# 05-nRF52840.net
KiCad netlist of a schematic drawn in Altium Designer
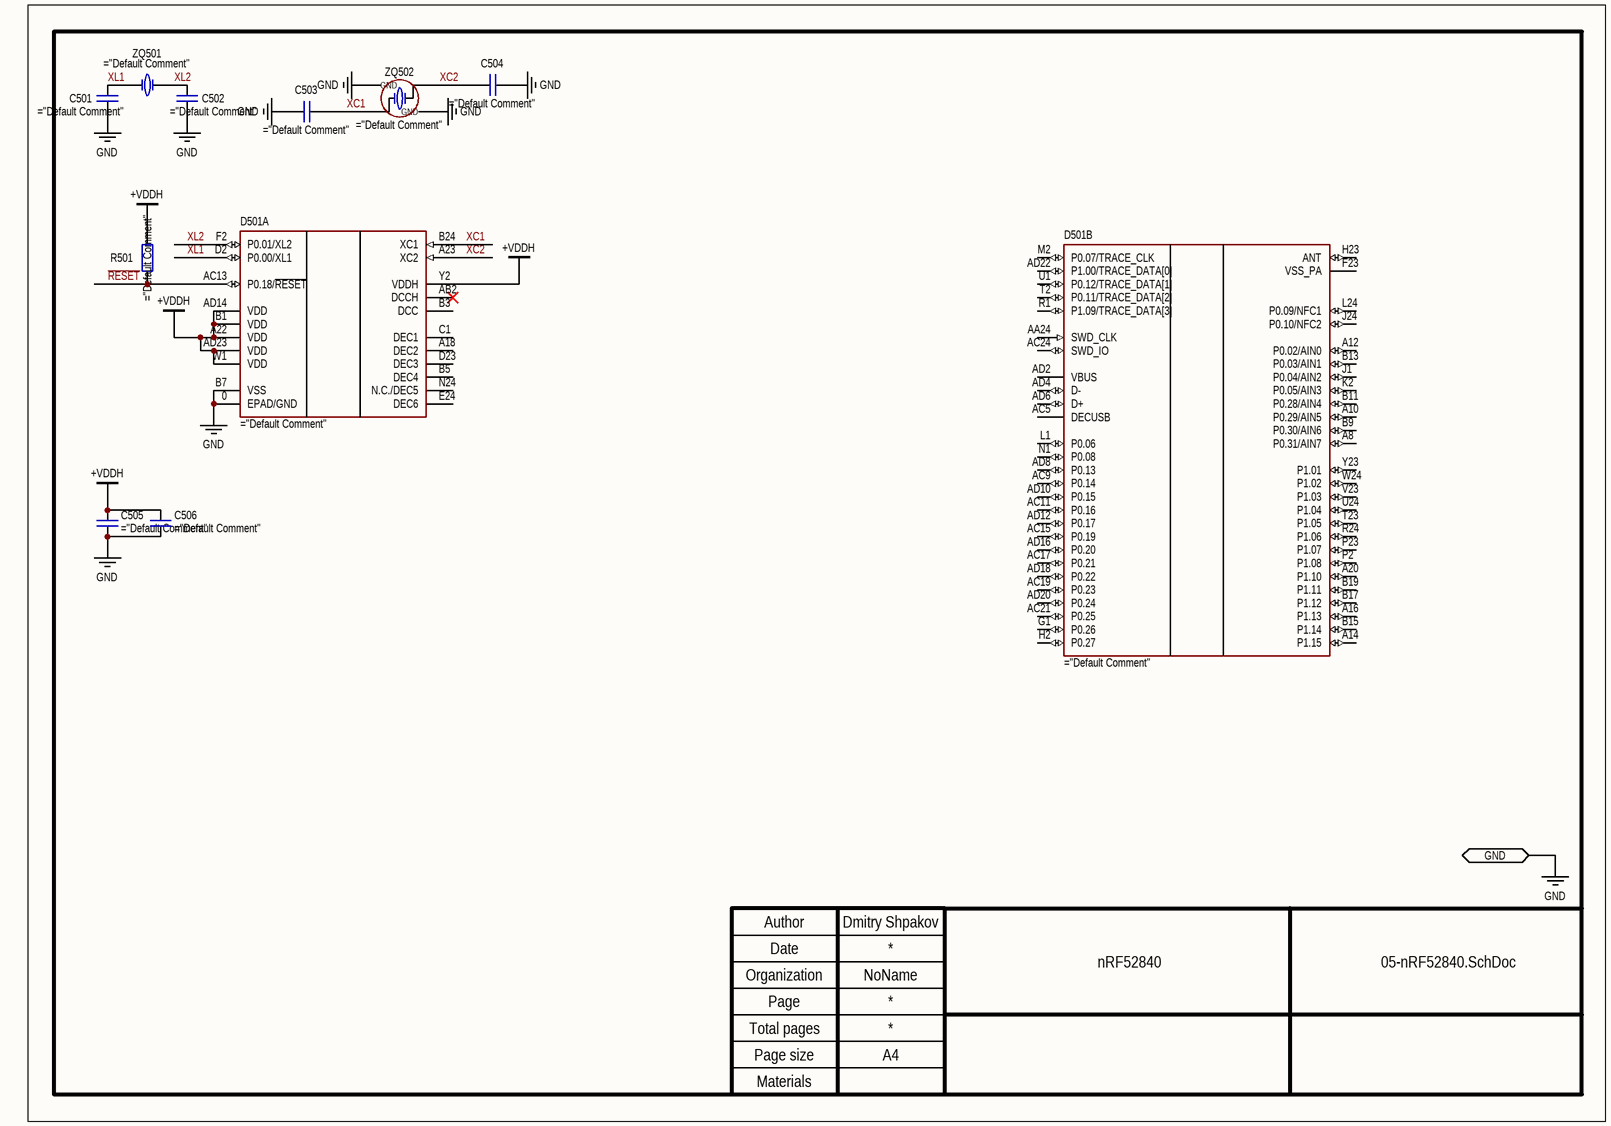
[diagram p0: 05-nRF52840.SchDoc]

(export (version "E")
  (design (tool "Eeschema 10.0.6"))
  (components
    (comp (ref "C501")
      (value "~")
      (footprint "CAP0402MD")
      (description "CAP CER 12PF 50V C0G/NPO 0402")
      (fields (field (name "MANUFACTURER") "YAGEO") (field (name "TOLERANCE") "5 %"))
      (libsource (lib "Capacitors") (part "CC0402JRNPO9BN120"))
    )
    (comp (ref "C502")
      (value "~")
      (footprint "CAP0402MD")
      (description "CAP CER 12PF 50V C0G/NPO 0402")
      (fields (field (name "MANUFACTURER") "YAGEO") (field (name "TOLERANCE") "5 %"))
      (libsource (lib "Capacitors") (part "CC0402JRNPO9BN120"))
    )
    (comp (ref "C503")
      (value "~")
      (footprint "CAP0402MD")
      (description "CAP CER 12PF 50V C0G/NPO 0402")
      (fields (field (name "MANUFACTURER") "YAGEO") (field (name "TOLERANCE") "5 %"))
      (libsource (lib "Capacitors") (part "CC0402JRNPO9BN120"))
    )
    (comp (ref "C504")
      (value "~")
      (footprint "CAP0402MD")
      (description "CAP CER 12PF 50V C0G/NPO 0402")
      (fields (field (name "MANUFACTURER") "YAGEO") (field (name "TOLERANCE") "5 %"))
      (libsource (lib "Capacitors") (part "CC0402JRNPO9BN120"))
    )
    (comp (ref "C505")
      (value "~")
      (footprint "CAP0603HD")
      (description "CAP CER 0.1UF 16V X7R 0603")
      (fields (field (name "MANUFACTURER") "YAGEO") (field (name "TOLERANCE") "10 %"))
      (libsource (lib "Capacitors") (part "CC0603KRX7R7BB104"))
    )
    (comp (ref "C506")
      (value "~")
      (footprint "CAP0603HD")
      (description "CAP CER 0.1UF 16V X7R 0603")
      (fields (field (name "MANUFACTURER") "YAGEO") (field (name "TOLERANCE") "10 %"))
      (libsource (lib "Capacitors") (part "CC0603KRX7R7BB104"))
    )
    (comp (ref "D501")
      (value "~")
      (footprint "nRF52840-QIAA")
      (description "IC RF TXRX+MCU 802.15.4 73VFQFN")
      (fields (field (name "MANUFACTURER") "Nordic Semiconductor ASA") (field (name "TOLERANCE") "* %"))
      (libsource (lib "ICs") (part "NRF52840-QIAA-R7"))
    )
    (comp (ref "R501")
      (value "~")
      (footprint "0402")
      (description "RES 10K OHM 5% 1/16W 0402")
      (fields (field (name "MANUFACTURER") "YAGEO") (field (name "TOLERANCE") "5 %"))
      (libsource (lib "Resistors") (part "RC0402JR-0710KL"))
    )
    (comp (ref "ZQ501")
      (value "~")
      (footprint "ECS-.327-9-16-TR")
      (description "CRYSTAL 32.7680KHZ 9PF SMD")
      (fields (field (name "MANUFACTURER") "ECS Inc.") (field (name "TOLERANCE") "20 ppm"))
      (libsource (lib "Oscillators") (part "ECS-.327-9-16-TR"))
    )
    (comp (ref "ZQ502")
      (value "~")
      (footprint "ECS-320-8-37B-CKY-TR")
      (description "CRYSTAL 32.0000MHZ 8PF SMD")
      (fields (field (name "MANUFACTURER") "ECS Inc.") (field (name "TOLERANCE") "10 ppm"))
      (libsource (lib "Oscillators") (part "ECS-320-8-37B-CKY-TR"))
    )
  )
  (nets
    (net (code "1") (name "+VDDH") (class "Default")
      (node (ref "C505") (pin "2") (pintype "passive"))
      (node (ref "C506") (pin "2") (pintype "passive"))
      (node (ref "D501") (pin "A22") (pinfunction "VDD_A22") (pintype "power_in"))
      (node (ref "D501") (pin "AD14") (pinfunction "VDD_AD14") (pintype "power_in"))
      (node (ref "D501") (pin "AD23") (pinfunction "VDD_AD23") (pintype "power_in"))
      (node (ref "D501") (pin "B1") (pinfunction "VDD_B1") (pintype "power_in"))
      (node (ref "D501") (pin "W1") (pinfunction "VDD_W1") (pintype "power_in"))
      (node (ref "D501") (pin "Y2") (pinfunction "VDDH_Y2") (pintype "power_in"))
      (node (ref "R501") (pin "2") (pinfunction "2_2") (pintype "passive"))
    )
    (net (code "2") (name "/RESET") (class "Default")
      (node (ref "D501") (pin "AC13") (pinfunction "P0.18/~{RESET}_AC13") (pintype "bidirectional"))
      (node (ref "R501") (pin "1") (pinfunction "1_1") (pintype "passive"))
    )
    (net (code "3") (name "/XC1") (class "Default")
      (node (ref "C503") (pin "2") (pintype "passive"))
      (node (ref "D501") (pin "B24") (pinfunction "XC1_B24") (pintype "input"))
      (node (ref "ZQ502") (pin "1") (pinfunction "1_1") (pintype "passive"))
    )
    (net (code "4") (name "/XC2") (class "Default")
      (node (ref "C504") (pin "2") (pintype "passive"))
      (node (ref "D501") (pin "A23") (pinfunction "XC2_A23") (pintype "input"))
      (node (ref "ZQ502") (pin "3") (pinfunction "3_3") (pintype "passive"))
    )
    (net (code "5") (name "/XL1") (class "Default")
      (node (ref "C501") (pin "2") (pintype "passive"))
      (node (ref "D501") (pin "D2") (pinfunction "P0.00/XL1_D2") (pintype "bidirectional"))
      (node (ref "ZQ501") (pin "2") (pinfunction "2_2") (pintype "passive"))
    )
    (net (code "6") (name "/XL2") (class "Default")
      (node (ref "C502") (pin "2") (pintype "passive"))
      (node (ref "D501") (pin "F2") (pinfunction "P0.01/XL2_F2") (pintype "bidirectional"))
      (node (ref "ZQ501") (pin "1") (pinfunction "1_1") (pintype "passive"))
    )
    (net (code "7") (name "GND") (class "Default")
      (node (ref "C501") (pin "1") (pintype "passive"))
      (node (ref "C502") (pin "1") (pintype "passive"))
      (node (ref "C503") (pin "1") (pintype "passive"))
      (node (ref "C504") (pin "1") (pintype "passive"))
      (node (ref "C505") (pin "1") (pintype "passive"))
      (node (ref "C506") (pin "1") (pintype "passive"))
      (node (ref "D501") (pin "0") (pinfunction "EPAD/GND_0") (pintype "passive"))
      (node (ref "D501") (pin "B7") (pinfunction "VSS_B7") (pintype "passive"))
      (node (ref "ZQ502") (pin "2") (pinfunction "2_2") (pintype "passive"))
      (node (ref "ZQ502") (pin "4") (pinfunction "4_4") (pintype "passive"))
    )
    (net (code "8") (name "unconnected-(D501A-DCC-PadB3)") (class "Default")
      (node (ref "D501") (pin "B3") (pinfunction "DCC_B3") (pintype "power_in"))
    )
    (net (code "9") (name "unconnected-(D501A-DCCH-PadAB2)") (class "Default")
      (node (ref "D501") (pin "AB2") (pinfunction "DCCH_AB2") (pintype "power_in+no_connect"))
    )
    (net (code "10") (name "unconnected-(D501A-DEC1-PadC1)") (class "Default")
      (node (ref "D501") (pin "C1") (pinfunction "DEC1_C1") (pintype "power_in"))
    )
    (net (code "11") (name "unconnected-(D501A-DEC2-PadA18)") (class "Default")
      (node (ref "D501") (pin "A18") (pinfunction "DEC2_A18") (pintype "power_in"))
    )
    (net (code "12") (name "unconnected-(D501A-DEC3-PadD23)") (class "Default")
      (node (ref "D501") (pin "D23") (pinfunction "DEC3_D23") (pintype "power_in"))
    )
    (net (code "13") (name "unconnected-(D501A-DEC4-PadB5)") (class "Default")
      (node (ref "D501") (pin "B5") (pinfunction "DEC4_B5") (pintype "power_in"))
    )
    (net (code "14") (name "unconnected-(D501A-DEC6-PadE24)") (class "Default")
      (node (ref "D501") (pin "E24") (pinfunction "DEC6_E24") (pintype "power_in"))
    )
    (net (code "15") (name "unconnected-(D501A-N.C.{slash}DEC5-PadN24)") (class "Default")
      (node (ref "D501") (pin "N24") (pinfunction "N.C./DEC5_N24") (pintype "power_in"))
    )
    (net (code "16") (name "unconnected-(D501B-ANT-PadH23)") (class "Default")
      (node (ref "D501") (pin "H23") (pinfunction "ANT_H23") (pintype "bidirectional"))
    )
    (net (code "17") (name "unconnected-(D501B-D+-PadAD6)") (class "Default")
      (node (ref "D501") (pin "AD6") (pinfunction "D+_AD6") (pintype "bidirectional"))
    )
    (net (code "18") (name "unconnected-(D501B-D--PadAD4)") (class "Default")
      (node (ref "D501") (pin "AD4") (pinfunction "D-_AD4") (pintype "bidirectional"))
    )
    (net (code "19") (name "unconnected-(D501B-DECUSB-PadAC5)") (class "Default")
      (node (ref "D501") (pin "AC5") (pinfunction "DECUSB_AC5") (pintype "power_in"))
    )
    (net (code "20") (name "unconnected-(D501B-P0.02{slash}AIN0-PadA12)") (class "Default")
      (node (ref "D501") (pin "A12") (pinfunction "P0.02/AIN0_A12") (pintype "bidirectional"))
    )
    (net (code "21") (name "unconnected-(D501B-P0.03{slash}AIN1-PadB13)") (class "Default")
      (node (ref "D501") (pin "B13") (pinfunction "P0.03/AIN1_B13") (pintype "bidirectional"))
    )
    (net (code "22") (name "unconnected-(D501B-P0.04{slash}AIN2-PadJ1)") (class "Default")
      (node (ref "D501") (pin "J1") (pinfunction "P0.04/AIN2_J1") (pintype "bidirectional"))
    )
    (net (code "23") (name "unconnected-(D501B-P0.05{slash}AIN3-PadK2)") (class "Default")
      (node (ref "D501") (pin "K2") (pinfunction "P0.05/AIN3_K2") (pintype "bidirectional"))
    )
    (net (code "24") (name "unconnected-(D501B-P0.06-PadL1)") (class "Default")
      (node (ref "D501") (pin "L1") (pinfunction "P0.06_L1") (pintype "bidirectional"))
    )
    (net (code "25") (name "unconnected-(D501B-P0.07{slash}TRACE_CLK-PadM2)") (class "Default")
      (node (ref "D501") (pin "M2") (pinfunction "P0.07/TRACE_CLK_M2") (pintype "bidirectional"))
    )
    (net (code "26") (name "unconnected-(D501B-P0.08-PadN1)") (class "Default")
      (node (ref "D501") (pin "N1") (pinfunction "P0.08_N1") (pintype "bidirectional"))
    )
    (net (code "27") (name "unconnected-(D501B-P0.09{slash}NFC1-PadL24)") (class "Default")
      (node (ref "D501") (pin "L24") (pinfunction "P0.09/NFC1_L24") (pintype "bidirectional"))
    )
    (net (code "28") (name "unconnected-(D501B-P0.10{slash}NFC2-PadJ24)") (class "Default")
      (node (ref "D501") (pin "J24") (pinfunction "P0.10/NFC2_J24") (pintype "bidirectional"))
    )
    (net (code "29") (name "unconnected-(D501B-P0.11{slash}TRACE_DATA[2]-PadT2)") (class "Default")
      (node (ref "D501") (pin "T2") (pinfunction "P0.11/TRACE_DATA[2]_T2") (pintype "bidirectional"))
    )
    (net (code "30") (name "unconnected-(D501B-P0.12{slash}TRACE_DATA[1]-PadU1)") (class "Default")
      (node (ref "D501") (pin "U1") (pinfunction "P0.12/TRACE_DATA[1]_U1") (pintype "bidirectional"))
    )
    (net (code "31") (name "unconnected-(D501B-P0.13-PadAD8)") (class "Default")
      (node (ref "D501") (pin "AD8") (pinfunction "P0.13_AD8") (pintype "bidirectional"))
    )
    (net (code "32") (name "unconnected-(D501B-P0.14-PadAC9)") (class "Default")
      (node (ref "D501") (pin "AC9") (pinfunction "P0.14_AC9") (pintype "bidirectional"))
    )
    (net (code "33") (name "unconnected-(D501B-P0.15-PadAD10)") (class "Default")
      (node (ref "D501") (pin "AD10") (pinfunction "P0.15_AD10") (pintype "bidirectional"))
    )
    (net (code "34") (name "unconnected-(D501B-P0.16-PadAC11)") (class "Default")
      (node (ref "D501") (pin "AC11") (pinfunction "P0.16_AC11") (pintype "bidirectional"))
    )
    (net (code "35") (name "unconnected-(D501B-P0.17-PadAD12)") (class "Default")
      (node (ref "D501") (pin "AD12") (pinfunction "P0.17_AD12") (pintype "bidirectional"))
    )
    (net (code "36") (name "unconnected-(D501B-P0.19-PadAC15)") (class "Default")
      (node (ref "D501") (pin "AC15") (pinfunction "P0.19_AC15") (pintype "bidirectional"))
    )
    (net (code "37") (name "unconnected-(D501B-P0.20-PadAD16)") (class "Default")
      (node (ref "D501") (pin "AD16") (pinfunction "P0.20_AD16") (pintype "bidirectional"))
    )
    (net (code "38") (name "unconnected-(D501B-P0.21-PadAC17)") (class "Default")
      (node (ref "D501") (pin "AC17") (pinfunction "P0.21_AC17") (pintype "bidirectional"))
    )
    (net (code "39") (name "unconnected-(D501B-P0.22-PadAD18)") (class "Default")
      (node (ref "D501") (pin "AD18") (pinfunction "P0.22_AD18") (pintype "bidirectional"))
    )
    (net (code "40") (name "unconnected-(D501B-P0.23-PadAC19)") (class "Default")
      (node (ref "D501") (pin "AC19") (pinfunction "P0.23_AC19") (pintype "bidirectional"))
    )
    (net (code "41") (name "unconnected-(D501B-P0.24-PadAD20)") (class "Default")
      (node (ref "D501") (pin "AD20") (pinfunction "P0.24_AD20") (pintype "bidirectional"))
    )
    (net (code "42") (name "unconnected-(D501B-P0.25-PadAC21)") (class "Default")
      (node (ref "D501") (pin "AC21") (pinfunction "P0.25_AC21") (pintype "bidirectional"))
    )
    (net (code "43") (name "unconnected-(D501B-P0.26-PadG1)") (class "Default")
      (node (ref "D501") (pin "G1") (pinfunction "P0.26_G1") (pintype "bidirectional"))
    )
    (net (code "44") (name "unconnected-(D501B-P0.27-PadH2)") (class "Default")
      (node (ref "D501") (pin "H2") (pinfunction "P0.27_H2") (pintype "bidirectional"))
    )
    (net (code "45") (name "unconnected-(D501B-P0.28{slash}AIN4-PadB11)") (class "Default")
      (node (ref "D501") (pin "B11") (pinfunction "P0.28/AIN4_B11") (pintype "bidirectional"))
    )
    (net (code "46") (name "unconnected-(D501B-P0.29{slash}AIN5-PadA10)") (class "Default")
      (node (ref "D501") (pin "A10") (pinfunction "P0.29/AIN5_A10") (pintype "bidirectional"))
    )
    (net (code "47") (name "unconnected-(D501B-P0.30{slash}AIN6-PadB9)") (class "Default")
      (node (ref "D501") (pin "B9") (pinfunction "P0.30/AIN6_B9") (pintype "bidirectional"))
    )
    (net (code "48") (name "unconnected-(D501B-P0.31{slash}AIN7-PadA8)") (class "Default")
      (node (ref "D501") (pin "A8") (pinfunction "P0.31/AIN7_A8") (pintype "bidirectional"))
    )
    (net (code "49") (name "unconnected-(D501B-P1.00{slash}TRACE_DATA[0]-PadAD22)") (class "Default")
      (node (ref "D501") (pin "AD22") (pinfunction "P1.00/TRACE_DATA[0]_AD22") (pintype "bidirectional"))
    )
    (net (code "50") (name "unconnected-(D501B-P1.01-PadY23)") (class "Default")
      (node (ref "D501") (pin "Y23") (pinfunction "P1.01_Y23") (pintype "bidirectional"))
    )
    (net (code "51") (name "unconnected-(D501B-P1.02-PadW24)") (class "Default")
      (node (ref "D501") (pin "W24") (pinfunction "P1.02_W24") (pintype "bidirectional"))
    )
    (net (code "52") (name "unconnected-(D501B-P1.03-PadV23)") (class "Default")
      (node (ref "D501") (pin "V23") (pinfunction "P1.03_V23") (pintype "bidirectional"))
    )
    (net (code "53") (name "unconnected-(D501B-P1.04-PadU24)") (class "Default")
      (node (ref "D501") (pin "U24") (pinfunction "P1.04_U24") (pintype "bidirectional"))
    )
    (net (code "54") (name "unconnected-(D501B-P1.05-PadT23)") (class "Default")
      (node (ref "D501") (pin "T23") (pinfunction "P1.05_T23") (pintype "bidirectional"))
    )
    (net (code "55") (name "unconnected-(D501B-P1.06-PadR24)") (class "Default")
      (node (ref "D501") (pin "R24") (pinfunction "P1.06_R24") (pintype "bidirectional"))
    )
    (net (code "56") (name "unconnected-(D501B-P1.07-PadP23)") (class "Default")
      (node (ref "D501") (pin "P23") (pinfunction "P1.07_P23") (pintype "bidirectional"))
    )
    (net (code "57") (name "unconnected-(D501B-P1.08-PadP2)") (class "Default")
      (node (ref "D501") (pin "P2") (pinfunction "P1.08_P2") (pintype "bidirectional"))
    )
    (net (code "58") (name "unconnected-(D501B-P1.09{slash}TRACE_DATA[3]-PadR1)") (class "Default")
      (node (ref "D501") (pin "R1") (pinfunction "P1.09/TRACE_DATA[3]_R1") (pintype "bidirectional"))
    )
    (net (code "59") (name "unconnected-(D501B-P1.10-PadA20)") (class "Default")
      (node (ref "D501") (pin "A20") (pinfunction "P1.10_A20") (pintype "bidirectional"))
    )
    (net (code "60") (name "unconnected-(D501B-P1.11-PadB19)") (class "Default")
      (node (ref "D501") (pin "B19") (pinfunction "P1.11_B19") (pintype "bidirectional"))
    )
    (net (code "61") (name "unconnected-(D501B-P1.12-PadB17)") (class "Default")
      (node (ref "D501") (pin "B17") (pinfunction "P1.12_B17") (pintype "bidirectional"))
    )
    (net (code "62") (name "unconnected-(D501B-P1.13-PadA16)") (class "Default")
      (node (ref "D501") (pin "A16") (pinfunction "P1.13_A16") (pintype "bidirectional"))
    )
    (net (code "63") (name "unconnected-(D501B-P1.14-PadB15)") (class "Default")
      (node (ref "D501") (pin "B15") (pinfunction "P1.14_B15") (pintype "bidirectional"))
    )
    (net (code "64") (name "unconnected-(D501B-P1.15-PadA14)") (class "Default")
      (node (ref "D501") (pin "A14") (pinfunction "P1.15_A14") (pintype "bidirectional"))
    )
    (net (code "65") (name "unconnected-(D501B-SWD_CLK-PadAA24)") (class "Default")
      (node (ref "D501") (pin "AA24") (pinfunction "SWD_CLK_AA24") (pintype "input"))
    )
    (net (code "66") (name "unconnected-(D501B-SWD_IO-PadAC24)") (class "Default")
      (node (ref "D501") (pin "AC24") (pinfunction "SWD_IO_AC24") (pintype "bidirectional"))
    )
    (net (code "67") (name "unconnected-(D501B-VBUS-PadAD2)") (class "Default")
      (node (ref "D501") (pin "AD2") (pinfunction "VBUS_AD2") (pintype "power_in"))
    )
    (net (code "68") (name "unconnected-(D501B-VSS_PA-PadF23)") (class "Default")
      (node (ref "D501") (pin "F23") (pinfunction "VSS_PA_F23") (pintype "power_in"))
    )
  )
)
